# MicroMod_Sno_Processor.net
KiCad netlist of a schematic drawn in EAGLE
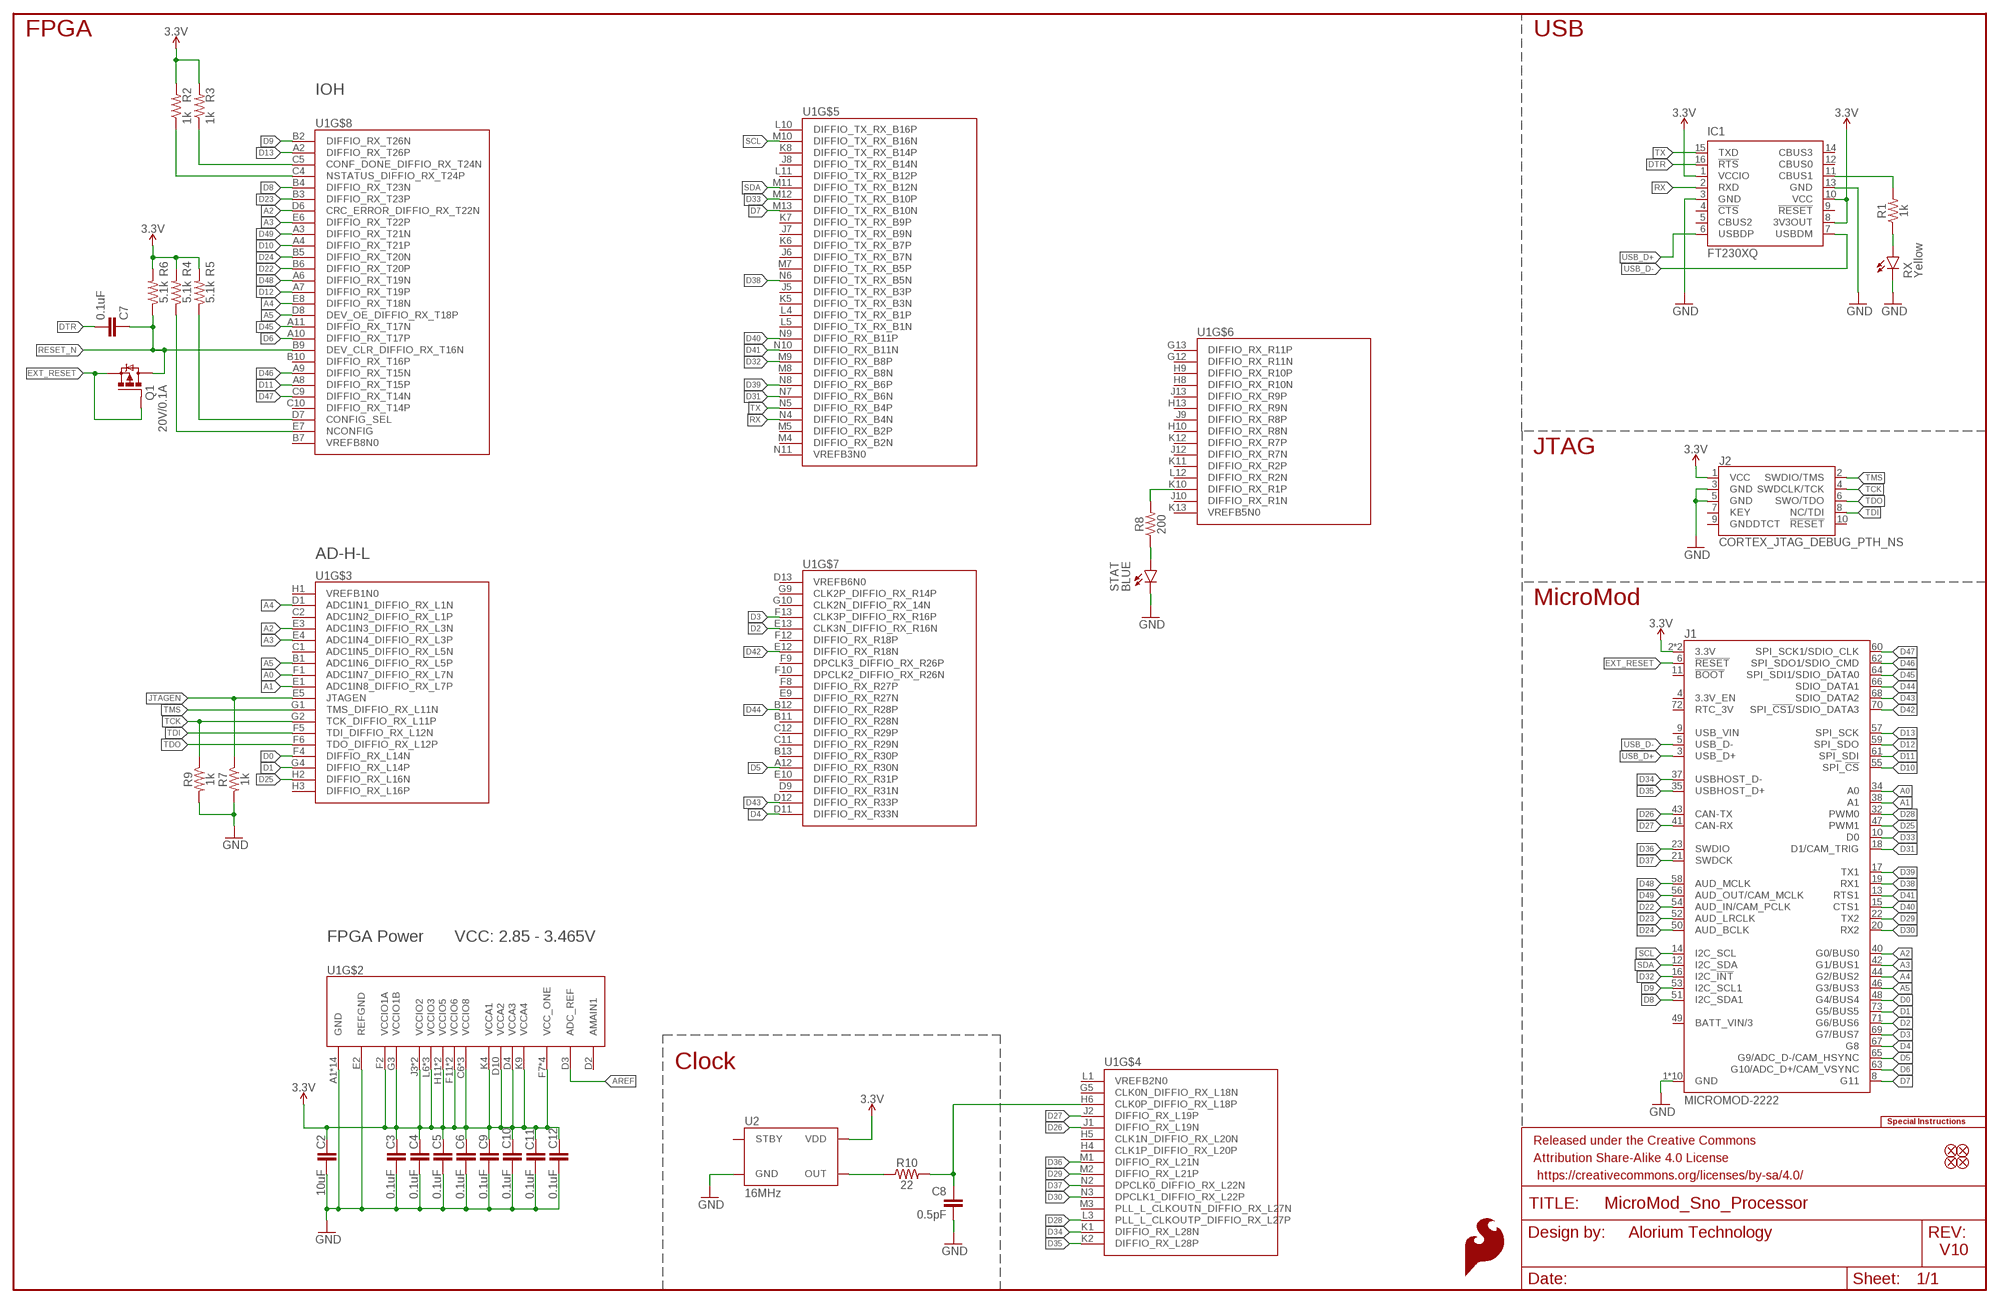
[diagram p0: schematic, sheet 1]

(export (version "E")
  (design (tool "Eeschema 10.0.6"))
  (components
    (comp (ref "C2")
      (value "10uF")
      (footprint "eagle-import:0402-TIGHT")
      (libsource (lib "eagle-import") (part "10UF-0402T-6.3V-20%"))
    )
    (comp (ref "C3")
      (value "0.1uF")
      (footprint "eagle-import:0402-TIGHT")
      (libsource (lib "eagle-import") (part "0.1UF-0402T-6.3V-10%-X7R"))
    )
    (comp (ref "C4")
      (value "0.1uF")
      (footprint "eagle-import:0402-TIGHT")
      (libsource (lib "eagle-import") (part "0.1UF-0402T-6.3V-10%-X7R"))
    )
    (comp (ref "C5")
      (value "0.1uF")
      (footprint "eagle-import:0402-TIGHT")
      (libsource (lib "eagle-import") (part "0.1UF-0402T-6.3V-10%-X7R"))
    )
    (comp (ref "C6")
      (value "0.1uF")
      (footprint "eagle-import:0402-TIGHT")
      (libsource (lib "eagle-import") (part "0.1UF-0402T-6.3V-10%-X7R"))
    )
    (comp (ref "C7")
      (value "0.1uF")
      (footprint "eagle-import:0402-TIGHT")
      (libsource (lib "eagle-import") (part "0.1UF-0402T-6.3V-10%-X7R"))
    )
    (comp (ref "C8")
      (value "0.5pF")
      (footprint "eagle-import:0402-TIGHT")
      (libsource (lib "eagle-import") (part "0.5PF-0402_TIGHT-50V-PM0.05PF-NP0"))
    )
    (comp (ref "C9")
      (value "0.1uF")
      (footprint "eagle-import:0402-TIGHT")
      (libsource (lib "eagle-import") (part "0.1UF-0402T-6.3V-10%-X7R"))
    )
    (comp (ref "C10")
      (value "0.1uF")
      (footprint "eagle-import:0402-TIGHT")
      (libsource (lib "eagle-import") (part "0.1UF-0402T-6.3V-10%-X7R"))
    )
    (comp (ref "C11")
      (value "0.1uF")
      (footprint "eagle-import:0402-TIGHT")
      (libsource (lib "eagle-import") (part "0.1UF-0402T-6.3V-10%-X7R"))
    )
    (comp (ref "C12")
      (value "0.1uF")
      (footprint "eagle-import:0402-TIGHT")
      (libsource (lib "eagle-import") (part "0.1UF-0402T-6.3V-10%-X7R"))
    )
    (comp (ref "FID1")
      (value "FIDUCIAL1X2")
      (footprint "eagle-import:FIDUCIAL-1X2")
      (libsource (lib "eagle-import") (part "FIDUCIAL1X2"))
    )
    (comp (ref "FID2")
      (value "FIDUCIAL1X2")
      (footprint "eagle-import:FIDUCIAL-1X2")
      (libsource (lib "eagle-import") (part "FIDUCIAL1X2"))
    )
    (comp (ref "FID3")
      (value "FIDUCIAL1X2")
      (footprint "eagle-import:FIDUCIAL-1X2")
      (libsource (lib "eagle-import") (part "FIDUCIAL1X2"))
    )
    (comp (ref "FID4")
      (value "FIDUCIAL1X2")
      (footprint "eagle-import:FIDUCIAL-1X2")
      (libsource (lib "eagle-import") (part "FIDUCIAL1X2"))
    )
    (comp (ref "FRAME1")
      (value "FRAME-LEDGER")
      (footprint "eagle-import:CREATIVE_COMMONS")
      (libsource (lib "eagle-import") (part "FRAME-LEDGER"))
    )
    (comp (ref "IC1")
      (value "FT230XQ")
      (footprint "eagle-import:QFN16")
      (fields (field (name "DIGIKEY_PART") "768-1130-2-ND"))
      (libsource (lib "eagle-import") (part "FT230XQ"))
    )
    (comp (ref "J1")
      (value "MICROMOD-2222")
      (footprint "eagle-import:M.2-CARD-E-22")
      (libsource (lib "eagle-import") (part "MICROMOD-2222"))
    )
    (comp (ref "J2")
      (value "CORTEX_JTAG_DEBUG_PTH_NS")
      (footprint "eagle-import:2X5-PTH-1.27MM-NO_SILK")
      (libsource (lib "eagle-import") (part "CORTEX_JTAG_DEBUG_PTH_NS"))
    )
    (comp (ref "LOGO1")
      (value "SPECIAL_INSTRUCTIONS-ORDERING")
      (footprint "eagle-import:ORDERING_INSTRUCTIONS")
      (libsource (lib "eagle-import") (part "SPECIAL_INSTRUCTIONS-ORDERING"))
    )
    (comp (ref "LOGO2")
      (value "SFE_LOGO_FLAME.1_INCH")
      (footprint "eagle-import:SFE_LOGO_FLAME_.1")
      (libsource (lib "eagle-import") (part "SFE_LOGO_FLAME.1_INCH"))
    )
    (comp (ref "Q1")
      (value "20V/0.1A")
      (footprint "eagle-import:SOT-416")
      (libsource (lib "eagle-import") (part "RE1C001ZP"))
    )
    (comp (ref "R1")
      (value "1k")
      (footprint "eagle-import:0402-TIGHT")
      (libsource (lib "eagle-import") (part "1KOHM-0402T-1/16W-1%"))
    )
    (comp (ref "R2")
      (value "1k")
      (footprint "eagle-import:0402-TIGHT")
      (libsource (lib "eagle-import") (part "1KOHM-0402T-1/16W-1%"))
    )
    (comp (ref "R3")
      (value "1k")
      (footprint "eagle-import:0402-TIGHT")
      (libsource (lib "eagle-import") (part "1KOHM-0402T-1/16W-1%"))
    )
    (comp (ref "R4")
      (value "5.1k")
      (footprint "eagle-import:0402-TIGHT")
      (libsource (lib "eagle-import") (part "5.1KOHM-0402T-1/16W-1%"))
    )
    (comp (ref "R5")
      (value "5.1k")
      (footprint "eagle-import:0402-TIGHT")
      (libsource (lib "eagle-import") (part "5.1KOHM-0402T-1/16W-1%"))
    )
    (comp (ref "R6")
      (value "5.1k")
      (footprint "eagle-import:0402-TIGHT")
      (libsource (lib "eagle-import") (part "5.1KOHM-0402T-1/16W-1%"))
    )
    (comp (ref "R7")
      (value "1k")
      (footprint "eagle-import:0402-TIGHT")
      (libsource (lib "eagle-import") (part "1KOHM-0402T-1/16W-1%"))
    )
    (comp (ref "R8")
      (value "200")
      (footprint "eagle-import:0402-TIGHT")
      (libsource (lib "eagle-import") (part "200OHM-0402T-1/16W-1%"))
    )
    (comp (ref "R9")
      (value "1k")
      (footprint "eagle-import:0402-TIGHT")
      (libsource (lib "eagle-import") (part "1KOHM-0402T-1/16W-1%"))
    )
    (comp (ref "R10")
      (value "22")
      (footprint "eagle-import:0402-TIGHT")
      (libsource (lib "eagle-import") (part "22OHM-0402T-1/16W-1%"))
    )
    (comp (ref "RX")
      (value "Yellow")
      (footprint "eagle-import:LED-0603")
      (libsource (lib "eagle-import") (part "LED-YELLOW0603"))
    )
    (comp (ref "STAT")
      (value "BLUE")
      (footprint "eagle-import:LED-0603")
      (libsource (lib "eagle-import") (part "LED-BLUE0603"))
    )
    (comp (ref "U1")
      (value "10M08SA")
      (footprint "eagle-import:UBGA_169")
      (fields (field (name "DIGIKEY_PART") "544-3110-ND"))
      (libsource (lib "eagle-import") (part "10M08SA"))
    )
    (comp (ref "U2")
      (value "16MHz")
      (footprint "eagle-import:SMD20X16")
      (libsource (lib "eagle-import") (part "OSC_TINY_16SMD20X16"))
    )
  )
  (nets
    (net (code "1") (name "3.3V") (class "Default")
      (node (ref "C10") (pin "1") (pinfunction "1_1") (pintype "passive"))
      (node (ref "C11") (pin "1") (pinfunction "1_1") (pintype "passive"))
      (node (ref "C12") (pin "1") (pinfunction "1_1") (pintype "passive"))
      (node (ref "C2") (pin "1") (pinfunction "1_1") (pintype "passive"))
      (node (ref "C3") (pin "1") (pinfunction "1_1") (pintype "passive"))
      (node (ref "C4") (pin "1") (pinfunction "1_1") (pintype "passive"))
      (node (ref "C5") (pin "1") (pinfunction "1_1") (pintype "passive"))
      (node (ref "C6") (pin "1") (pinfunction "1_1") (pintype "passive"))
      (node (ref "C9") (pin "1") (pinfunction "1_1") (pintype "passive"))
      (node (ref "IC1") (pin "1") (pinfunction "VCCIO_1") (pintype "power_in"))
      (node (ref "IC1") (pin "10") (pinfunction "VCC_10") (pintype "power_in"))
      (node (ref "IC1") (pin "8") (pinfunction "3V3OUT_8") (pintype "output"))
      (node (ref "J1") (pin "2") (pinfunction "3.3V_2") (pintype "bidirectional"))
      (node (ref "J1") (pin "74") (pinfunction "3.3V_74") (pintype "bidirectional"))
      (node (ref "J2") (pin "1") (pinfunction "VCC_1") (pintype "bidirectional"))
      (node (ref "R2") (pin "2") (pinfunction "2_2") (pintype "passive"))
      (node (ref "R3") (pin "2") (pinfunction "2_2") (pintype "passive"))
      (node (ref "R4") (pin "2") (pinfunction "2_2") (pintype "passive"))
      (node (ref "R5") (pin "2") (pinfunction "2_2") (pintype "passive"))
      (node (ref "R6") (pin "2") (pinfunction "2_2") (pintype "passive"))
      (node (ref "U1") (pin "C6") (pinfunction "VCCIO8_C6") (pintype "bidirectional"))
      (node (ref "U1") (pin "C7") (pinfunction "VCCIO8_C7") (pintype "bidirectional"))
      (node (ref "U1") (pin "C8") (pinfunction "VCCIO8_C8") (pintype "bidirectional"))
      (node (ref "U1") (pin "D10") (pinfunction "VCCA2_D10") (pintype "bidirectional"))
      (node (ref "U1") (pin "D4") (pinfunction "VCCA3_D4") (pintype "bidirectional"))
      (node (ref "U1") (pin "F11") (pinfunction "VCCIO6_F11") (pintype "bidirectional"))
      (node (ref "U1") (pin "F2") (pinfunction "VCCIO1A_F2") (pintype "bidirectional"))
      (node (ref "U1") (pin "F7") (pinfunction "VCC_ONE_F7") (pintype "bidirectional"))
      (node (ref "U1") (pin "G11") (pinfunction "VCCIO6_G11") (pintype "bidirectional"))
      (node (ref "U1") (pin "G3") (pinfunction "VCCIO1B_G3") (pintype "bidirectional"))
      (node (ref "U1") (pin "G6") (pinfunction "VCC_ONE_G6") (pintype "bidirectional"))
      (node (ref "U1") (pin "G8") (pinfunction "VCC_ONE_G8") (pintype "bidirectional"))
      (node (ref "U1") (pin "H11") (pinfunction "VCCIO5_H11") (pintype "bidirectional"))
      (node (ref "U1") (pin "H7") (pinfunction "VCC_ONE_H7") (pintype "bidirectional"))
      (node (ref "U1") (pin "J11") (pinfunction "VCCIO5_J11") (pintype "bidirectional"))
      (node (ref "U1") (pin "J3") (pinfunction "VCCIO2_J3") (pintype "bidirectional"))
      (node (ref "U1") (pin "K3") (pinfunction "VCCIO2_K3") (pintype "bidirectional"))
      (node (ref "U1") (pin "K4") (pinfunction "VCCA1_K4") (pintype "bidirectional"))
      (node (ref "U1") (pin "K9") (pinfunction "VCCA4_K9") (pintype "bidirectional"))
      (node (ref "U1") (pin "L6") (pinfunction "VCCIO3_L6") (pintype "bidirectional"))
      (node (ref "U1") (pin "L7") (pinfunction "VCCIO3_L7") (pintype "bidirectional"))
      (node (ref "U1") (pin "L8") (pinfunction "VCCIO3_L8") (pintype "bidirectional"))
      (node (ref "U2") (pin "4") (pinfunction "VDD_4") (pintype "bidirectional"))
    )
    (net (code "2") (name "A0") (class "Default")
      (node (ref "J1") (pin "34") (pinfunction "A0_34") (pintype "bidirectional"))
      (node (ref "U1") (pin "F1") (pinfunction "ADC1IN7_DIFFIO_RX_L7N_F1") (pintype "bidirectional"))
    )
    (net (code "3") (name "A1") (class "Default")
      (node (ref "J1") (pin "38") (pinfunction "A1_38") (pintype "bidirectional"))
      (node (ref "U1") (pin "E1") (pinfunction "ADC1IN8_DIFFIO_RX_L7P_E1") (pintype "bidirectional"))
    )
    (net (code "4") (name "A2") (class "Default")
      (node (ref "J1") (pin "40") (pinfunction "G0/BUS0_40") (pintype "bidirectional"))
      (node (ref "U1") (pin "D6") (pinfunction "CRC_ERROR_DIFFIO_RX_T22N_D6") (pintype "bidirectional"))
      (node (ref "U1") (pin "E3") (pinfunction "ADC1IN3_DIFFIO_RX_L3N_E3") (pintype "bidirectional"))
    )
    (net (code "5") (name "A3") (class "Default")
      (node (ref "J1") (pin "42") (pinfunction "G1/BUS1_42") (pintype "bidirectional"))
      (node (ref "U1") (pin "E4") (pinfunction "ADC1IN4_DIFFIO_RX_L3P_E4") (pintype "bidirectional"))
      (node (ref "U1") (pin "E6") (pinfunction "DIFFIO_RX_T22P_E6") (pintype "bidirectional"))
    )
    (net (code "6") (name "A4") (class "Default")
      (node (ref "J1") (pin "44") (pinfunction "G2/BUS2_44") (pintype "bidirectional"))
      (node (ref "U1") (pin "D1") (pinfunction "ADC1IN1_DIFFIO_RX_L1N_D1") (pintype "bidirectional"))
      (node (ref "U1") (pin "E8") (pinfunction "DIFFIO_RX_T18N_E8") (pintype "bidirectional"))
    )
    (net (code "7") (name "A5") (class "Default")
      (node (ref "J1") (pin "46") (pinfunction "G3/BUS3_46") (pintype "bidirectional"))
      (node (ref "U1") (pin "B1") (pinfunction "ADC1IN6_DIFFIO_RX_L5P_B1") (pintype "bidirectional"))
      (node (ref "U1") (pin "D8") (pinfunction "DEV_OE_DIFFIO_RX_T18P_D8") (pintype "bidirectional"))
    )
    (net (code "8") (name "AREF") (class "Default")
      (node (ref "U1") (pin "D3") (pinfunction "ADC_REF_D3") (pintype "bidirectional"))
    )
    (net (code "9") (name "D0") (class "Default")
      (node (ref "J1") (pin "48") (pinfunction "G4/BUS4_48") (pintype "bidirectional"))
      (node (ref "U1") (pin "F4") (pinfunction "DIFFIO_RX_L14N_F4") (pintype "bidirectional"))
    )
    (net (code "10") (name "D1") (class "Default")
      (node (ref "J1") (pin "73") (pinfunction "G5/BUS5_73") (pintype "bidirectional"))
      (node (ref "U1") (pin "G4") (pinfunction "DIFFIO_RX_L14P_G4") (pintype "bidirectional"))
    )
    (net (code "11") (name "D2") (class "Default")
      (node (ref "J1") (pin "71") (pinfunction "G6/BUS6_71") (pintype "bidirectional"))
      (node (ref "U1") (pin "E13") (pinfunction "CLK3N_DIFFIO_RX_R16N_E13") (pintype "bidirectional"))
    )
    (net (code "12") (name "D3") (class "Default")
      (node (ref "J1") (pin "69") (pinfunction "G7/BUS7_69") (pintype "bidirectional"))
      (node (ref "U1") (pin "F13") (pinfunction "CLK3P_DIFFIO_RX_R16P_F13") (pintype "bidirectional"))
    )
    (net (code "13") (name "D4") (class "Default")
      (node (ref "J1") (pin "67") (pinfunction "G8_67") (pintype "bidirectional"))
      (node (ref "U1") (pin "D11") (pinfunction "DIFFIO_RX_R33N_D11") (pintype "bidirectional"))
    )
    (net (code "14") (name "D5") (class "Default")
      (node (ref "J1") (pin "65") (pinfunction "G9/ADC_D-/CAM_HSYNC_65") (pintype "bidirectional"))
      (node (ref "U1") (pin "A12") (pinfunction "DIFFIO_RX_R30N_A12") (pintype "bidirectional"))
    )
    (net (code "15") (name "D6") (class "Default")
      (node (ref "J1") (pin "63") (pinfunction "G10/ADC_D+/CAM_VSYNC_63") (pintype "bidirectional"))
      (node (ref "U1") (pin "A10") (pinfunction "DIFFIO_RX_T17P_A10") (pintype "bidirectional"))
    )
    (net (code "16") (name "D7") (class "Default")
      (node (ref "J1") (pin "8") (pinfunction "G11_8") (pintype "bidirectional"))
      (node (ref "U1") (pin "M13") (pinfunction "DIFFIO_TX_RX_B10N_M13") (pintype "bidirectional"))
    )
    (net (code "17") (name "D8") (class "Default")
      (node (ref "J1") (pin "51") (pinfunction "I2C_SDA1_51") (pintype "bidirectional"))
      (node (ref "U1") (pin "B4") (pinfunction "DIFFIO_RX_T23N_B4") (pintype "bidirectional"))
    )
    (net (code "18") (name "D9") (class "Default")
      (node (ref "J1") (pin "53") (pinfunction "I2C_SCL1_53") (pintype "bidirectional"))
      (node (ref "U1") (pin "B2") (pinfunction "DIFFIO_RX_T26N_B2") (pintype "bidirectional"))
    )
    (net (code "19") (name "D10") (class "Default")
      (node (ref "J1") (pin "55") (pinfunction "SPI_~{CS}_55") (pintype "bidirectional"))
      (node (ref "U1") (pin "A4") (pinfunction "DIFFIO_RX_T21P_A4") (pintype "bidirectional"))
    )
    (net (code "20") (name "D11") (class "Default")
      (node (ref "J1") (pin "61") (pinfunction "SPI_SDI_61") (pintype "bidirectional"))
      (node (ref "U1") (pin "A8") (pinfunction "DIFFIO_RX_T15P_A8") (pintype "bidirectional"))
    )
    (net (code "21") (name "D12") (class "Default")
      (node (ref "J1") (pin "59") (pinfunction "SPI_SDO_59") (pintype "bidirectional"))
      (node (ref "U1") (pin "A7") (pinfunction "DIFFIO_RX_T19P_A7") (pintype "bidirectional"))
    )
    (net (code "22") (name "D13") (class "Default")
      (node (ref "J1") (pin "57") (pinfunction "SPI_SCK_57") (pintype "bidirectional"))
      (node (ref "U1") (pin "A2") (pinfunction "DIFFIO_RX_T26P_A2") (pintype "bidirectional"))
    )
    (net (code "23") (name "D22") (class "Default")
      (node (ref "J1") (pin "54") (pinfunction "AUD_IN/CAM_PCLK_54") (pintype "bidirectional"))
      (node (ref "U1") (pin "B6") (pinfunction "DIFFIO_RX_T20P_B6") (pintype "bidirectional"))
    )
    (net (code "24") (name "D23") (class "Default")
      (node (ref "J1") (pin "52") (pinfunction "AUD_LRCLK_52") (pintype "bidirectional"))
      (node (ref "U1") (pin "B3") (pinfunction "DIFFIO_RX_T23P_B3") (pintype "bidirectional"))
    )
    (net (code "25") (name "D24") (class "Default")
      (node (ref "J1") (pin "50") (pinfunction "AUD_BCLK_50") (pintype "bidirectional"))
      (node (ref "U1") (pin "B5") (pinfunction "DIFFIO_RX_T20N_B5") (pintype "bidirectional"))
    )
    (net (code "26") (name "D25") (class "Default")
      (node (ref "J1") (pin "47") (pinfunction "PWM1_47") (pintype "bidirectional"))
      (node (ref "U1") (pin "H2") (pinfunction "DIFFIO_RX_L16N_H2") (pintype "bidirectional"))
    )
    (net (code "27") (name "D26") (class "Default")
      (node (ref "J1") (pin "43") (pinfunction "CAN-TX_43") (pintype "bidirectional"))
      (node (ref "U1") (pin "J1") (pinfunction "DIFFIO_RX_L19N_J1") (pintype "bidirectional"))
    )
    (net (code "28") (name "D27") (class "Default")
      (node (ref "J1") (pin "41") (pinfunction "CAN-RX_41") (pintype "bidirectional"))
      (node (ref "U1") (pin "J2") (pinfunction "DIFFIO_RX_L19P_J2") (pintype "bidirectional"))
    )
    (net (code "29") (name "D28") (class "Default")
      (node (ref "J1") (pin "32") (pinfunction "PWM0_32") (pintype "bidirectional"))
      (node (ref "U1") (pin "L3") (pinfunction "PLL_L_CLKOUTP_DIFFIO_RX_L27P_L3") (pintype "bidirectional"))
    )
    (net (code "30") (name "D29") (class "Default")
      (node (ref "J1") (pin "22") (pinfunction "TX2_22") (pintype "bidirectional"))
      (node (ref "U1") (pin "M2") (pinfunction "DIFFIO_RX_L21P_M2") (pintype "bidirectional"))
    )
    (net (code "31") (name "D30") (class "Default")
      (node (ref "J1") (pin "20") (pinfunction "RX2_20") (pintype "bidirectional"))
      (node (ref "U1") (pin "N3") (pinfunction "DPCLK1_DIFFIO_RX_L22P_N3") (pintype "bidirectional"))
    )
    (net (code "32") (name "D31") (class "Default")
      (node (ref "J1") (pin "18") (pinfunction "D1/CAM_TRIG_18") (pintype "bidirectional"))
      (node (ref "U1") (pin "N7") (pinfunction "DIFFIO_RX_B6N_N7") (pintype "bidirectional"))
    )
    (net (code "33") (name "D32") (class "Default")
      (node (ref "J1") (pin "16") (pinfunction "I2C_~{INT}_16") (pintype "bidirectional"))
      (node (ref "U1") (pin "M9") (pinfunction "DIFFIO_RX_B8P_M9") (pintype "bidirectional"))
    )
    (net (code "34") (name "D33") (class "Default")
      (node (ref "J1") (pin "10") (pinfunction "D0_10") (pintype "bidirectional"))
      (node (ref "U1") (pin "M12") (pinfunction "DIFFIO_TX_RX_B10P_M12") (pintype "bidirectional"))
    )
    (net (code "35") (name "D34") (class "Default")
      (node (ref "J1") (pin "37") (pinfunction "USBHOST_D-_37") (pintype "bidirectional"))
      (node (ref "U1") (pin "K1") (pinfunction "DIFFIO_RX_L28N_K1") (pintype "bidirectional"))
    )
    (net (code "36") (name "D35") (class "Default")
      (node (ref "J1") (pin "35") (pinfunction "USBHOST_D+_35") (pintype "bidirectional"))
      (node (ref "U1") (pin "K2") (pinfunction "DIFFIO_RX_L28P_K2") (pintype "bidirectional"))
    )
    (net (code "37") (name "D36") (class "Default")
      (node (ref "J1") (pin "23") (pinfunction "SWDIO_23") (pintype "bidirectional"))
      (node (ref "U1") (pin "M1") (pinfunction "DIFFIO_RX_L21N_M1") (pintype "bidirectional"))
    )
    (net (code "38") (name "D37") (class "Default")
      (node (ref "J1") (pin "21") (pinfunction "SWDCK_21") (pintype "bidirectional"))
      (node (ref "U1") (pin "N2") (pinfunction "DPCLK0_DIFFIO_RX_L22N_N2") (pintype "bidirectional"))
    )
    (net (code "39") (name "D38") (class "Default")
      (node (ref "J1") (pin "19") (pinfunction "RX1_19") (pintype "bidirectional"))
      (node (ref "U1") (pin "N6") (pinfunction "DIFFIO_TX_RX_B5N_N6") (pintype "bidirectional"))
    )
    (net (code "40") (name "D39") (class "Default")
      (node (ref "J1") (pin "17") (pinfunction "TX1_17") (pintype "bidirectional"))
      (node (ref "U1") (pin "N8") (pinfunction "DIFFIO_RX_B6P_N8") (pintype "bidirectional"))
    )
    (net (code "41") (name "D40") (class "Default")
      (node (ref "J1") (pin "15") (pinfunction "CTS1_15") (pintype "bidirectional"))
      (node (ref "U1") (pin "N9") (pinfunction "DIFFIO_RX_B11P_N9") (pintype "bidirectional"))
    )
    (net (code "42") (name "D41") (class "Default")
      (node (ref "J1") (pin "13") (pinfunction "RTS1_13") (pintype "bidirectional"))
      (node (ref "U1") (pin "N10") (pinfunction "DIFFIO_RX_B11N_N10") (pintype "bidirectional"))
    )
    (net (code "43") (name "D42") (class "Default")
      (node (ref "J1") (pin "70") (pinfunction "SPI_~{CS1}/SDIO_DATA3_70") (pintype "bidirectional"))
      (node (ref "U1") (pin "E12") (pinfunction "DIFFIO_RX_R18N_E12") (pintype "bidirectional"))
    )
    (net (code "44") (name "D43") (class "Default")
      (node (ref "J1") (pin "68") (pinfunction "SDIO_DATA2_68") (pintype "bidirectional"))
      (node (ref "U1") (pin "D12") (pinfunction "DIFFIO_RX_R33P_D12") (pintype "bidirectional"))
    )
    (net (code "45") (name "D44") (class "Default")
      (node (ref "J1") (pin "66") (pinfunction "SDIO_DATA1_66") (pintype "bidirectional"))
      (node (ref "U1") (pin "B12") (pinfunction "DIFFIO_RX_R28P_B12") (pintype "bidirectional"))
    )
    (net (code "46") (name "D45") (class "Default")
      (node (ref "J1") (pin "64") (pinfunction "SPI_SDI1/SDIO_DATA0_64") (pintype "bidirectional"))
      (node (ref "U1") (pin "A11") (pinfunction "DIFFIO_RX_T17N_A11") (pintype "bidirectional"))
    )
    (net (code "47") (name "D46") (class "Default")
      (node (ref "J1") (pin "62") (pinfunction "SPI_SDO1/SDIO_CMD_62") (pintype "bidirectional"))
      (node (ref "U1") (pin "A9") (pinfunction "DIFFIO_RX_T15N_A9") (pintype "bidirectional"))
    )
    (net (code "48") (name "D47") (class "Default")
      (node (ref "J1") (pin "60") (pinfunction "SPI_SCK1/SDIO_CLK_60") (pintype "bidirectional"))
      (node (ref "U1") (pin "C9") (pinfunction "DIFFIO_RX_T14N_C9") (pintype "bidirectional"))
    )
    (net (code "49") (name "D48") (class "Default")
      (node (ref "J1") (pin "58") (pinfunction "AUD_MCLK_58") (pintype "bidirectional"))
      (node (ref "U1") (pin "A6") (pinfunction "DIFFIO_RX_T19N_A6") (pintype "bidirectional"))
    )
    (net (code "50") (name "D49") (class "Default")
      (node (ref "J1") (pin "56") (pinfunction "AUD_OUT/CAM_MCLK_56") (pintype "bidirectional"))
      (node (ref "U1") (pin "A3") (pinfunction "DIFFIO_RX_T21N_A3") (pintype "bidirectional"))
    )
    (net (code "51") (name "DTR") (class "Default")
      (node (ref "C7") (pin "2") (pinfunction "2_2") (pintype "passive"))
      (node (ref "IC1") (pin "16") (pinfunction "~{RTS}_16") (pintype "output"))
    )
    (net (code "52") (name "EXT_RESET") (class "Default")
      (node (ref "J1") (pin "6") (pinfunction "~{RESET}_6") (pintype "bidirectional"))
      (node (ref "Q1") (pin "P1") (pinfunction "G_P1") (pintype "passive"))
      (node (ref "Q1") (pin "P2") (pinfunction "S_P2") (pintype "passive"))
    )
    (net (code "53") (name "GND") (class "Default")
      (node (ref "C10") (pin "2") (pinfunction "2_2") (pintype "passive"))
      (node (ref "C11") (pin "2") (pinfunction "2_2") (pintype "passive"))
      (node (ref "C12") (pin "2") (pinfunction "2_2") (pintype "passive"))
      (node (ref "C2") (pin "2") (pinfunction "2_2") (pintype "passive"))
      (node (ref "C3") (pin "2") (pinfunction "2_2") (pintype "passive"))
      (node (ref "C4") (pin "2") (pinfunction "2_2") (pintype "passive"))
      (node (ref "C5") (pin "2") (pinfunction "2_2") (pintype "passive"))
      (node (ref "C6") (pin "2") (pinfunction "2_2") (pintype "passive"))
      (node (ref "C8") (pin "2") (pinfunction "2_2") (pintype "passive"))
      (node (ref "C9") (pin "2") (pinfunction "2_2") (pintype "passive"))
      (node (ref "IC1") (pin "13") (pinfunction "GND_13") (pintype "power_in"))
      (node (ref "IC1") (pin "3") (pinfunction "GND_3") (pintype "power_in"))
      (node (ref "J1") (pin "1") (pinfunction "GND_1") (pintype "bidirectional"))
      (node (ref "J1") (pin "33") (pinfunction "GND_33") (pintype "bidirectional"))
      (node (ref "J1") (pin "36") (pinfunction "GND_36") (pintype "bidirectional"))
      (node (ref "J1") (pin "39") (pinfunction "GND_39") (pintype "bidirectional"))
      (node (ref "J1") (pin "45") (pinfunction "GND_45") (pintype "bidirectional"))
      (node (ref "J1") (pin "7") (pinfunction "GND_7") (pintype "bidirectional"))
      (node (ref "J1") (pin "75") (pinfunction "GND_75") (pintype "bidirectional"))
      (node (ref "J1") (pin "GND1") (pinfunction "GND_GND1") (pintype "bidirectional"))
      (node (ref "J1") (pin "GND2") (pinfunction "GND_GND2") (pintype "bidirectional"))
      (node (ref "J1") (pin "GND3") (pinfunction "GND_GND3") (pintype "bidirectional"))
      (node (ref "J2") (pin "3") (pinfunction "GND_3") (pintype "bidirectional"))
      (node (ref "J2") (pin "5") (pinfunction "GND_5") (pintype "bidirectional"))
      (node (ref "R7") (pin "2") (pinfunction "2_2") (pintype "passive"))
      (node (ref "R9") (pin "2") (pinfunction "2_2") (pintype "passive"))
      (node (ref "RX") (pin "C") (pinfunction "C_C") (pintype "passive"))
      (node (ref "STAT") (pin "C") (pinfunction "C_C") (pintype "passive"))
      (node (ref "U1") (pin "A1") (pinfunction "GND_A1") (pintype "bidirectional"))
      (node (ref "U1") (pin "A13") (pinfunction "GND_A13") (pintype "bidirectional"))
      (node (ref "U1") (pin "B8") (pinfunction "GND_B8") (pintype "bidirectional"))
      (node (ref "U1") (pin "C3") (pinfunction "GND_C3") (pintype "bidirectional"))
      (node (ref "U1") (pin "D5") (pinfunction "GND_D5") (pintype "bidirectional"))
      (node (ref "U1") (pin "E11") (pinfunction "GND_E11") (pintype "bidirectional"))
      (node (ref "U1") (pin "E2") (pinfunction "REFGND_E2") (pintype "bidirectional"))
      (node (ref "U1") (pin "F3") (pinfunction "GND_F3") (pintype "bidirectional"))
      (node (ref "U1") (pin "G7") (pinfunction "GND_G7") (pintype "bidirectional"))
      (node (ref "U1") (pin "H12") (pinfunction "GND_H12") (pintype "bidirectional"))
      (node (ref "U1") (pin "J4") (pinfunction "GND_J4") (pintype "bidirectional"))
      (node (ref "U1") (pin "L9") (pinfunction "GND_L9") (pintype "bidirectional"))
      (node (ref "U1") (pin "M6") (pinfunction "GND_M6") (pintype "bidirectional"))
      (node (ref "U1") (pin "N1") (pinfunction "GND_N1") (pintype "bidirectional"))
      (node (ref "U1") (pin "N13") (pinfunction "GND_N13") (pintype "bidirectional"))
      (node (ref "U2") (pin "2") (pinfunction "GND_2") (pintype "bidirectional"))
    )
    (net (code "54") (name "JTAGEN") (class "Default")
      (node (ref "R7") (pin "1") (pinfunction "1_1") (pintype "passive"))
      (node (ref "U1") (pin "E5") (pinfunction "JTAGEN_E5") (pintype "bidirectional"))
    )
    (net (code "55") (name "Net-(IC1-CBUS1)") (class "Default")
      (node (ref "IC1") (pin "11") (pinfunction "CBUS1_11") (pintype "bidirectional"))
      (node (ref "R1") (pin "2") (pinfunction "2_2") (pintype "passive"))
    )
    (net (code "56") (name "Net-(R1-Pad1)") (class "Default")
      (node (ref "R1") (pin "1") (pinfunction "1_1") (pintype "passive"))
      (node (ref "RX") (pin "A") (pinfunction "A_A") (pintype "passive"))
    )
    (net (code "57") (name "Net-(R8-Pad1)") (class "Default")
      (node (ref "R8") (pin "1") (pinfunction "1_1") (pintype "passive"))
      (node (ref "STAT") (pin "A") (pinfunction "A_A") (pintype "passive"))
    )
    (net (code "58") (name "Net-(U1C-CLK0P_DIFFIO_RX_L18P)") (class "Default")
      (node (ref "C8") (pin "1") (pinfunction "1_1") (pintype "passive"))
      (node (ref "R10") (pin "2") (pinfunction "2_2") (pintype "passive"))
      (node (ref "U1") (pin "H6") (pinfunction "CLK0P_DIFFIO_RX_L18P_H6") (pintype "bidirectional"))
    )
    (net (code "59") (name "Net-(U1E-DIFFIO_RX_R1P)") (class "Default")
      (node (ref "R8") (pin "2") (pinfunction "2_2") (pintype "passive"))
      (node (ref "U1") (pin "K10") (pinfunction "DIFFIO_RX_R1P_K10") (pintype "bidirectional"))
    )
    (net (code "60") (name "Net-(U1G-CONFIG_SEL)") (class "Default")
      (node (ref "R5") (pin "1") (pinfunction "1_1") (pintype "passive"))
      (node (ref "U1") (pin "D7") (pinfunction "CONFIG_SEL_D7") (pintype "bidirectional"))
    )
    (net (code "61") (name "Net-(U1G-CONF_DONE_DIFFIO_RX_T24N)") (class "Default")
      (node (ref "R3") (pin "1") (pinfunction "1_1") (pintype "passive"))
      (node (ref "U1") (pin "C5") (pinfunction "CONF_DONE_DIFFIO_RX_T24N_C5") (pintype "bidirectional"))
    )
    (net (code "62") (name "Net-(U1G-NCONFIG)") (class "Default")
      (node (ref "R4") (pin "1") (pinfunction "1_1") (pintype "passive"))
      (node (ref "U1") (pin "E7") (pinfunction "NCONFIG_E7") (pintype "bidirectional"))
    )
    (net (code "63") (name "Net-(U1G-NSTATUS_DIFFIO_RX_T24P)") (class "Default")
      (node (ref "R2") (pin "1") (pinfunction "1_1") (pintype "passive"))
      (node (ref "U1") (pin "C4") (pinfunction "NSTATUS_DIFFIO_RX_T24P_C4") (pintype "bidirectional"))
    )
    (net (code "64") (name "Net-(U2-OUT)") (class "Default")
      (node (ref "R10") (pin "1") (pinfunction "1_1") (pintype "passive"))
      (node (ref "U2") (pin "3") (pinfunction "OUT_3") (pintype "bidirectional"))
    )
    (net (code "65") (name "RESET_N") (class "Default")
      (node (ref "C7") (pin "1") (pinfunction "1_1") (pintype "passive"))
      (node (ref "Q1") (pin "P3") (pinfunction "D_P3") (pintype "passive"))
      (node (ref "R6") (pin "1") (pinfunction "1_1") (pintype "passive"))
      (node (ref "U1") (pin "B9") (pinfunction "DEV_CLR_DIFFIO_RX_T16N_B9") (pintype "bidirectional"))
    )
    (net (code "66") (name "RX") (class "Default")
      (node (ref "IC1") (pin "2") (pinfunction "RXD_2") (pintype "input"))
      (node (ref "U1") (pin "N4") (pinfunction "DIFFIO_RX_B4N_N4") (pintype "bidirectional"))
    )
    (net (code "67") (name "SCL") (class "Default")
      (node (ref "J1") (pin "14") (pinfunction "I2C_SCL_14") (pintype "bidirectional"))
      (node (ref "U1") (pin "M10") (pinfunction "DIFFIO_TX_RX_B16N_M10") (pintype "bidirectional"))
    )
    (net (code "68") (name "SDA") (class "Default")
      (node (ref "J1") (pin "12") (pinfunction "I2C_SDA_12") (pintype "bidirectional"))
      (node (ref "U1") (pin "M11") (pinfunction "DIFFIO_TX_RX_B12N_M11") (pintype "bidirectional"))
    )
    (net (code "69") (name "TCK") (class "Default")
      (node (ref "J2") (pin "4") (pinfunction "SWDCLK/TCK_4") (pintype "bidirectional"))
      (node (ref "R9") (pin "1") (pinfunction "1_1") (pintype "passive"))
      (node (ref "U1") (pin "G2") (pinfunction "TCK_DIFFIO_RX_L11P_G2") (pintype "bidirectional"))
    )
    (net (code "70") (name "TDI") (class "Default")
      (node (ref "J2") (pin "8") (pinfunction "NC/TDI_8") (pintype "bidirectional"))
      (node (ref "U1") (pin "F5") (pinfunction "TDI_DIFFIO_RX_L12N_F5") (pintype "bidirectional"))
    )
    (net (code "71") (name "TDO") (class "Default")
      (node (ref "J2") (pin "6") (pinfunction "SWO/TDO_6") (pintype "bidirectional"))
      (node (ref "U1") (pin "F6") (pinfunction "TDO_DIFFIO_RX_L12P_F6") (pintype "bidirectional"))
    )
    (net (code "72") (name "TMS") (class "Default")
      (node (ref "J2") (pin "2") (pinfunction "SWDIO/TMS_2") (pintype "bidirectional"))
      (node (ref "U1") (pin "G1") (pinfunction "TMS_DIFFIO_RX_L11N_G1") (pintype "bidirectional"))
    )
    (net (code "73") (name "TX") (class "Default")
      (node (ref "IC1") (pin "15") (pinfunction "TXD_15") (pintype "output"))
      (node (ref "U1") (pin "N5") (pinfunction "DIFFIO_RX_B4P_N5") (pintype "bidirectional"))
    )
    (net (code "74") (name "USB_D+") (class "Default")
      (node (ref "IC1") (pin "6") (pinfunction "USBDP_6") (pintype "input"))
      (node (ref "J1") (pin "3") (pinfunction "USB_D+_3") (pintype "bidirectional"))
    )
    (net (code "75") (name "USB_D-") (class "Default")
      (node (ref "IC1") (pin "7") (pinfunction "USBDM_7") (pintype "input"))
      (node (ref "J1") (pin "5") (pinfunction "USB_D-_5") (pintype "bidirectional"))
    )
    (net (code "76") (name "unconnected-(IC1-CBUS0-Pad12)") (class "Default")
      (node (ref "IC1") (pin "12") (pinfunction "CBUS0_12") (pintype "bidirectional"))
    )
    (net (code "77") (name "unconnected-(IC1-CBUS2-Pad5)") (class "Default")
      (node (ref "IC1") (pin "5") (pinfunction "CBUS2_5") (pintype "bidirectional"))
    )
    (net (code "78") (name "unconnected-(IC1-CBUS3-Pad14)") (class "Default")
      (node (ref "IC1") (pin "14") (pinfunction "CBUS3_14") (pintype "bidirectional"))
    )
    (net (code "79") (name "unconnected-(IC1-~{CTS}-Pad4)") (class "Default")
      (node (ref "IC1") (pin "4") (pinfunction "~{CTS}_4") (pintype "input"))
    )
    (net (code "80") (name "unconnected-(IC1-~{RESET}-Pad9)") (class "Default")
      (node (ref "IC1") (pin "9") (pinfunction "~{RESET}_9") (pintype "input"))
    )
    (net (code "81") (name "unconnected-(J1-3.3V_EN-Pad4)") (class "Default")
      (node (ref "J1") (pin "4") (pinfunction "3.3V_EN_4") (pintype "bidirectional"))
    )
    (net (code "82") (name "unconnected-(J1-BATT_VIN{slash}3-Pad49)") (class "Default")
      (node (ref "J1") (pin "49") (pinfunction "BATT_VIN/3_49") (pintype "bidirectional"))
    )
    (net (code "83") (name "unconnected-(J1-RTC_3V-Pad72)") (class "Default")
      (node (ref "J1") (pin "72") (pinfunction "RTC_3V_72") (pintype "bidirectional"))
    )
    (net (code "84") (name "unconnected-(J1-USB_VIN-Pad9)") (class "Default")
      (node (ref "J1") (pin "9") (pinfunction "USB_VIN_9") (pintype "bidirectional"))
    )
    (net (code "85") (name "unconnected-(J1-~{BOOT}-Pad11)") (class "Default")
      (node (ref "J1") (pin "11") (pinfunction "~{BOOT}_11") (pintype "bidirectional"))
    )
    (net (code "86") (name "unconnected-(J2-GNDDTCT-Pad9)") (class "Default")
      (node (ref "J2") (pin "9") (pinfunction "GNDDTCT_9") (pintype "bidirectional"))
    )
    (net (code "87") (name "unconnected-(J2-KEY-Pad7)") (class "Default")
      (node (ref "J2") (pin "7") (pinfunction "KEY_7") (pintype "bidirectional"))
    )
    (net (code "88") (name "unconnected-(J2-~{RESET}-Pad10)") (class "Default")
      (node (ref "J2") (pin "10") (pinfunction "~{RESET}_10") (pintype "bidirectional"))
    )
    (net (code "89") (name "unconnected-(U1A-AMAIN1-PadD2)") (class "Default")
      (node (ref "U1") (pin "D2") (pinfunction "AMAIN1_D2") (pintype "bidirectional"))
    )
    (net (code "90") (name "unconnected-(U1B-ADC1IN2_DIFFIO_RX_L1P-PadC2)") (class "Default")
      (node (ref "U1") (pin "C2") (pinfunction "ADC1IN2_DIFFIO_RX_L1P_C2") (pintype "bidirectional"))
    )
    (net (code "91") (name "unconnected-(U1B-ADC1IN5_DIFFIO_RX_L5N-PadC1)") (class "Default")
      (node (ref "U1") (pin "C1") (pinfunction "ADC1IN5_DIFFIO_RX_L5N_C1") (pintype "bidirectional"))
    )
    (net (code "92") (name "unconnected-(U1B-DIFFIO_RX_L16P-PadH3)") (class "Default")
      (node (ref "U1") (pin "H3") (pinfunction "DIFFIO_RX_L16P_H3") (pintype "bidirectional"))
    )
    (net (code "93") (name "unconnected-(U1B-VREFB1N0-PadH1)") (class "Default")
      (node (ref "U1") (pin "H1") (pinfunction "VREFB1N0_H1") (pintype "bidirectional"))
    )
    (net (code "94") (name "unconnected-(U1C-CLK0N_DIFFIO_RX_L18N-PadG5)") (class "Default")
      (node (ref "U1") (pin "G5") (pinfunction "CLK0N_DIFFIO_RX_L18N_G5") (pintype "bidirectional"))
    )
    (net (code "95") (name "unconnected-(U1C-CLK1N_DIFFIO_RX_L20N-PadH5)") (class "Default")
      (node (ref "U1") (pin "H5") (pinfunction "CLK1N_DIFFIO_RX_L20N_H5") (pintype "bidirectional"))
    )
    (net (code "96") (name "unconnected-(U1C-CLK1P_DIFFIO_RX_L20P-PadH4)") (class "Default")
      (node (ref "U1") (pin "H4") (pinfunction "CLK1P_DIFFIO_RX_L20P_H4") (pintype "bidirectional"))
    )
    (net (code "97") (name "unconnected-(U1C-PLL_L_CLKOUTN_DIFFIO_RX_L27N-PadM3)") (class "Default")
      (node (ref "U1") (pin "M3") (pinfunction "PLL_L_CLKOUTN_DIFFIO_RX_L27N_M3") (pintype "bidirectional"))
    )
    (net (code "98") (name "unconnected-(U1C-VREFB2N0-PadL1)") (class "Default")
      (node (ref "U1") (pin "L1") (pinfunction "VREFB2N0_L1") (pintype "bidirectional"))
    )
    (net (code "99") (name "unconnected-(U1D-DIFFIO_RX_B2N-PadM4)") (class "Default")
      (node (ref "U1") (pin "M4") (pinfunction "DIFFIO_RX_B2N_M4") (pintype "bidirectional"))
    )
    (net (code "100") (name "unconnected-(U1D-DIFFIO_RX_B2P-PadM5)") (class "Default")
      (node (ref "U1") (pin "M5") (pinfunction "DIFFIO_RX_B2P_M5") (pintype "bidirectional"))
    )
    (net (code "101") (name "unconnected-(U1D-DIFFIO_RX_B8N-PadM8)") (class "Default")
      (node (ref "U1") (pin "M8") (pinfunction "DIFFIO_RX_B8N_M8") (pintype "bidirectional"))
    )
    (net (code "102") (name "unconnected-(U1D-DIFFIO_TX_RX_B1N-PadL5)") (class "Default")
      (node (ref "U1") (pin "L5") (pinfunction "DIFFIO_TX_RX_B1N_L5") (pintype "bidirectional"))
    )
    (net (code "103") (name "unconnected-(U1D-DIFFIO_TX_RX_B1P-PadL4)") (class "Default")
      (node (ref "U1") (pin "L4") (pinfunction "DIFFIO_TX_RX_B1P_L4") (pintype "bidirectional"))
    )
    (net (code "104") (name "unconnected-(U1D-DIFFIO_TX_RX_B3N-PadK5)") (class "Default")
      (node (ref "U1") (pin "K5") (pinfunction "DIFFIO_TX_RX_B3N_K5") (pintype "bidirectional"))
    )
    (net (code "105") (name "unconnected-(U1D-DIFFIO_TX_RX_B3P-PadJ5)") (class "Default")
      (node (ref "U1") (pin "J5") (pinfunction "DIFFIO_TX_RX_B3P_J5") (pintype "bidirectional"))
    )
    (net (code "106") (name "unconnected-(U1D-DIFFIO_TX_RX_B5P-PadM7)") (class "Default")
      (node (ref "U1") (pin "M7") (pinfunction "DIFFIO_TX_RX_B5P_M7") (pintype "bidirectional"))
    )
    (net (code "107") (name "unconnected-(U1D-DIFFIO_TX_RX_B7N-PadJ6)") (class "Default")
      (node (ref "U1") (pin "J6") (pinfunction "DIFFIO_TX_RX_B7N_J6") (pintype "bidirectional"))
    )
    (net (code "108") (name "unconnected-(U1D-DIFFIO_TX_RX_B7P-PadK6)") (class "Default")
      (node (ref "U1") (pin "K6") (pinfunction "DIFFIO_TX_RX_B7P_K6") (pintype "bidirectional"))
    )
    (net (code "109") (name "unconnected-(U1D-DIFFIO_TX_RX_B9N-PadJ7)") (class "Default")
      (node (ref "U1") (pin "J7") (pinfunction "DIFFIO_TX_RX_B9N_J7") (pintype "bidirectional"))
    )
    (net (code "110") (name "unconnected-(U1D-DIFFIO_TX_RX_B9P-PadK7)") (class "Default")
      (node (ref "U1") (pin "K7") (pinfunction "DIFFIO_TX_RX_B9P_K7") (pintype "bidirectional"))
    )
    (net (code "111") (name "unconnected-(U1D-DIFFIO_TX_RX_B12P-PadL11)") (class "Default")
      (node (ref "U1") (pin "L11") (pinfunction "DIFFIO_TX_RX_B12P_L11") (pintype "bidirectional"))
    )
    (net (code "112") (name "unconnected-(U1D-DIFFIO_TX_RX_B14N-PadJ8)") (class "Default")
      (node (ref "U1") (pin "J8") (pinfunction "DIFFIO_TX_RX_B14N_J8") (pintype "bidirectional"))
    )
    (net (code "113") (name "unconnected-(U1D-DIFFIO_TX_RX_B14P-PadK8)") (class "Default")
      (node (ref "U1") (pin "K8") (pinfunction "DIFFIO_TX_RX_B14P_K8") (pintype "bidirectional"))
    )
    (net (code "114") (name "unconnected-(U1D-DIFFIO_TX_RX_B16P-PadL10)") (class "Default")
      (node (ref "U1") (pin "L10") (pinfunction "DIFFIO_TX_RX_B16P_L10") (pintype "bidirectional"))
    )
    (net (code "115") (name "unconnected-(U1D-VREFB3N0-PadN11)") (class "Default")
      (node (ref "U1") (pin "N11") (pinfunction "VREFB3N0_N11") (pintype "bidirectional"))
    )
    (net (code "116") (name "unconnected-(U1E-DIFFIO_RX_R1N-PadJ10)") (class "Default")
      (node (ref "U1") (pin "J10") (pinfunction "DIFFIO_RX_R1N_J10") (pintype "bidirectional"))
    )
    (net (code "117") (name "unconnected-(U1E-DIFFIO_RX_R2N-PadL12)") (class "Default")
      (node (ref "U1") (pin "L12") (pinfunction "DIFFIO_RX_R2N_L12") (pintype "bidirectional"))
    )
    (net (code "118") (name "unconnected-(U1E-DIFFIO_RX_R2P-PadK11)") (class "Default")
      (node (ref "U1") (pin "K11") (pinfunction "DIFFIO_RX_R2P_K11") (pintype "bidirectional"))
    )
    (net (code "119") (name "unconnected-(U1E-DIFFIO_RX_R7N-PadJ12)") (class "Default")
      (node (ref "U1") (pin "J12") (pinfunction "DIFFIO_RX_R7N_J12") (pintype "bidirectional"))
    )
    (net (code "120") (name "unconnected-(U1E-DIFFIO_RX_R7P-PadK12)") (class "Default")
      (node (ref "U1") (pin "K12") (pinfunction "DIFFIO_RX_R7P_K12") (pintype "bidirectional"))
    )
    (net (code "121") (name "unconnected-(U1E-DIFFIO_RX_R8N-PadH10)") (class "Default")
      (node (ref "U1") (pin "H10") (pinfunction "DIFFIO_RX_R8N_H10") (pintype "bidirectional"))
    )
    (net (code "122") (name "unconnected-(U1E-DIFFIO_RX_R8P-PadJ9)") (class "Default")
      (node (ref "U1") (pin "J9") (pinfunction "DIFFIO_RX_R8P_J9") (pintype "bidirectional"))
    )
    (net (code "123") (name "unconnected-(U1E-DIFFIO_RX_R9N-PadH13)") (class "Default")
      (node (ref "U1") (pin "H13") (pinfunction "DIFFIO_RX_R9N_H13") (pintype "bidirectional"))
    )
    (net (code "124") (name "unconnected-(U1E-DIFFIO_RX_R9P-PadJ13)") (class "Default")
      (node (ref "U1") (pin "J13") (pinfunction "DIFFIO_RX_R9P_J13") (pintype "bidirectional"))
    )
    (net (code "125") (name "unconnected-(U1E-DIFFIO_RX_R10N-PadH8)") (class "Default")
      (node (ref "U1") (pin "H8") (pinfunction "DIFFIO_RX_R10N_H8") (pintype "bidirectional"))
    )
    (net (code "126") (name "unconnected-(U1E-DIFFIO_RX_R10P-PadH9)") (class "Default")
      (node (ref "U1") (pin "H9") (pinfunction "DIFFIO_RX_R10P_H9") (pintype "bidirectional"))
    )
    (net (code "127") (name "unconnected-(U1E-DIFFIO_RX_R11N-PadG12)") (class "Default")
      (node (ref "U1") (pin "G12") (pinfunction "DIFFIO_RX_R11N_G12") (pintype "bidirectional"))
    )
    (net (code "128") (name "unconnected-(U1E-DIFFIO_RX_R11P-PadG13)") (class "Default")
      (node (ref "U1") (pin "G13") (pinfunction "DIFFIO_RX_R11P_G13") (pintype "bidirectional"))
    )
    (net (code "129") (name "unconnected-(U1E-VREFB5N0-PadK13)") (class "Default")
      (node (ref "U1") (pin "K13") (pinfunction "VREFB5N0_K13") (pintype "bidirectional"))
    )
    (net (code "130") (name "unconnected-(U1F-CLK2N_DIFFIO_RX_14N-PadG10)") (class "Default")
      (node (ref "U1") (pin "G10") (pinfunction "CLK2N_DIFFIO_RX_14N_G10") (pintype "bidirectional"))
    )
    (net (code "131") (name "unconnected-(U1F-CLK2P_DIFFIO_RX_R14P-PadG9)") (class "Default")
      (node (ref "U1") (pin "G9") (pinfunction "CLK2P_DIFFIO_RX_R14P_G9") (pintype "bidirectional"))
    )
    (net (code "132") (name "unconnected-(U1F-DIFFIO_RX_R18P-PadF12)") (class "Default")
      (node (ref "U1") (pin "F12") (pinfunction "DIFFIO_RX_R18P_F12") (pintype "bidirectional"))
    )
    (net (code "133") (name "unconnected-(U1F-DIFFIO_RX_R27N-PadE9)") (class "Default")
      (node (ref "U1") (pin "E9") (pinfunction "DIFFIO_RX_R27N_E9") (pintype "bidirectional"))
    )
    (net (code "134") (name "unconnected-(U1F-DIFFIO_RX_R27P-PadF8)") (class "Default")
      (node (ref "U1") (pin "F8") (pinfunction "DIFFIO_RX_R27P_F8") (pintype "bidirectional"))
    )
    (net (code "135") (name "unconnected-(U1F-DIFFIO_RX_R28N-PadB11)") (class "Default")
      (node (ref "U1") (pin "B11") (pinfunction "DIFFIO_RX_R28N_B11") (pintype "bidirectional"))
    )
    (net (code "136") (name "unconnected-(U1F-DIFFIO_RX_R29N-PadC11)") (class "Default")
      (node (ref "U1") (pin "C11") (pinfunction "DIFFIO_RX_R29N_C11") (pintype "bidirectional"))
    )
    (net (code "137") (name "unconnected-(U1F-DIFFIO_RX_R29P-PadC12)") (class "Default")
      (node (ref "U1") (pin "C12") (pinfunction "DIFFIO_RX_R29P_C12") (pintype "bidirectional"))
    )
    (net (code "138") (name "unconnected-(U1F-DIFFIO_RX_R30P-PadB13)") (class "Default")
      (node (ref "U1") (pin "B13") (pinfunction "DIFFIO_RX_R30P_B13") (pintype "bidirectional"))
    )
    (net (code "139") (name "unconnected-(U1F-DIFFIO_RX_R31N-PadD9)") (class "Default")
      (node (ref "U1") (pin "D9") (pinfunction "DIFFIO_RX_R31N_D9") (pintype "bidirectional"))
    )
    (net (code "140") (name "unconnected-(U1F-DIFFIO_RX_R31P-PadE10)") (class "Default")
      (node (ref "U1") (pin "E10") (pinfunction "DIFFIO_RX_R31P_E10") (pintype "bidirectional"))
    )
    (net (code "141") (name "unconnected-(U1F-DPCLK2_DIFFIO_RX_R26N-PadF10)") (class "Default")
      (node (ref "U1") (pin "F10") (pinfunction "DPCLK2_DIFFIO_RX_R26N_F10") (pintype "bidirectional"))
    )
    (net (code "142") (name "unconnected-(U1F-DPCLK3_DIFFIO_RX_R26P-PadF9)") (class "Default")
      (node (ref "U1") (pin "F9") (pinfunction "DPCLK3_DIFFIO_RX_R26P_F9") (pintype "bidirectional"))
    )
    (net (code "143") (name "unconnected-(U1F-VREFB6N0-PadD13)") (class "Default")
      (node (ref "U1") (pin "D13") (pinfunction "VREFB6N0_D13") (pintype "bidirectional"))
    )
    (net (code "144") (name "unconnected-(U1G-DIFFIO_RX_T14P-PadC10)") (class "Default")
      (node (ref "U1") (pin "C10") (pinfunction "DIFFIO_RX_T14P_C10") (pintype "bidirectional"))
    )
    (net (code "145") (name "unconnected-(U1G-DIFFIO_RX_T16P-PadB10)") (class "Default")
      (node (ref "U1") (pin "B10") (pinfunction "DIFFIO_RX_T16P_B10") (pintype "bidirectional"))
    )
    (net (code "146") (name "unconnected-(U1G-VREFB8N0-PadB7)") (class "Default")
      (node (ref "U1") (pin "B7") (pinfunction "VREFB8N0_B7") (pintype "bidirectional"))
    )
    (net (code "147") (name "unconnected-(U2-STBY-Pad1)") (class "Default")
      (node (ref "U2") (pin "1") (pinfunction "STBY_1") (pintype "bidirectional"))
    )
  )
)
